# main.net
KiCad netlist of a schematic drawn in Altium Designer
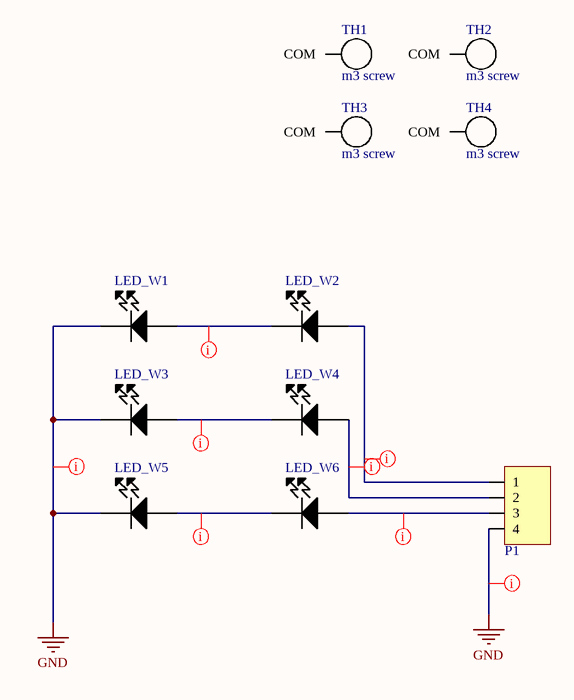
[diagram p0: main.SchDoc]

(export (version "E")
  (design (tool "Eeschema 10.0.6"))
  (components
    (comp (ref "LED_W1")
      (value "MP-3030-210H-40-95")
      (footprint "MP-3030-210H-40-95")
      (description "White 4000K neutral 1.5W 95CRI SMT3030 LED 6V 150mA")
      (libsource (lib "ScienceComponents") (part "MP-3030-210H-40-95"))
    )
    (comp (ref "LED_W2")
      (value "MP-3030-210H-40-95")
      (footprint "MP-3030-210H-40-95")
      (description "White 4000K neutral 1.5W 95CRI SMT3030 LED 6V 150mA")
      (libsource (lib "ScienceComponents") (part "MP-3030-210H-40-95"))
    )
    (comp (ref "LED_W3")
      (value "MP-3030-210H-40-95")
      (footprint "MP-3030-210H-40-95")
      (description "White 4000K neutral 1.5W 95CRI SMT3030 LED 6V 150mA")
      (libsource (lib "ScienceComponents") (part "MP-3030-210H-40-95"))
    )
    (comp (ref "LED_W4")
      (value "MP-3030-210H-40-95")
      (footprint "MP-3030-210H-40-95")
      (description "White 4000K neutral 1.5W 95CRI SMT3030 LED 6V 150mA")
      (libsource (lib "ScienceComponents") (part "MP-3030-210H-40-95"))
    )
    (comp (ref "LED_W5")
      (value "MP-3030-210H-40-95")
      (footprint "MP-3030-210H-40-95")
      (description "White 4000K neutral 1.5W 95CRI SMT3030 LED 6V 150mA")
      (libsource (lib "ScienceComponents") (part "MP-3030-210H-40-95"))
    )
    (comp (ref "LED_W6")
      (value "MP-3030-210H-40-95")
      (footprint "MP-3030-210H-40-95")
      (description "White 4000K neutral 1.5W 95CRI SMT3030 LED 6V 150mA")
      (libsource (lib "ScienceComponents") (part "MP-3030-210H-40-95"))
    )
    (comp (ref "P1")
      (value "Mini-Fit Jr 4 Pos")
      (footprint "MOLEX 0039281043")
      (libsource (lib "RSX_Connectors") (part "Molex 0039281043"))
    )
    (comp (ref "TH1")
      (value "m3 screw")
      (footprint "m3screw")
      (libsource (lib "ScienceComponents") (part "m3 screw"))
    )
    (comp (ref "TH2")
      (value "m3 screw")
      (footprint "m3screw")
      (libsource (lib "ScienceComponents") (part "m3 screw"))
    )
    (comp (ref "TH3")
      (value "m3 screw")
      (footprint "m3screw")
      (libsource (lib "ScienceComponents") (part "m3 screw"))
    )
    (comp (ref "TH4")
      (value "m3 screw")
      (footprint "m3screw")
      (libsource (lib "ScienceComponents") (part "m3 screw"))
    )
  )
  (nets
    (net (code "1") (name "GND") (class "Default")
      (node (ref "LED_W1") (pin "1") (pinfunction "-_1") (pintype "passive"))
      (node (ref "LED_W3") (pin "1") (pinfunction "-_1") (pintype "passive"))
      (node (ref "LED_W5") (pin "1") (pinfunction "-_1") (pintype "passive"))
      (node (ref "P1") (pin "4") (pinfunction "4_4") (pintype "passive"))
    )
    (net (code "2") (name "Net-(LED_W1-+)") (class "Default")
      (node (ref "LED_W1") (pin "2") (pinfunction "+_2") (pintype "passive"))
      (node (ref "LED_W2") (pin "1") (pinfunction "-_1") (pintype "passive"))
    )
    (net (code "3") (name "Net-(LED_W2-+)") (class "Default")
      (node (ref "LED_W2") (pin "2") (pinfunction "+_2") (pintype "passive"))
      (node (ref "P1") (pin "1") (pinfunction "1_1") (pintype "passive"))
    )
    (net (code "4") (name "Net-(LED_W3-+)") (class "Default")
      (node (ref "LED_W3") (pin "2") (pinfunction "+_2") (pintype "passive"))
      (node (ref "LED_W4") (pin "1") (pinfunction "-_1") (pintype "passive"))
    )
    (net (code "5") (name "Net-(LED_W4-+)") (class "Default")
      (node (ref "LED_W4") (pin "2") (pinfunction "+_2") (pintype "passive"))
      (node (ref "P1") (pin "2") (pinfunction "2_2") (pintype "passive"))
    )
    (net (code "6") (name "Net-(LED_W5-+)") (class "Default")
      (node (ref "LED_W5") (pin "2") (pinfunction "+_2") (pintype "passive"))
      (node (ref "LED_W6") (pin "1") (pinfunction "-_1") (pintype "passive"))
    )
    (net (code "7") (name "Net-(LED_W6-+)") (class "Default")
      (node (ref "LED_W6") (pin "2") (pinfunction "+_2") (pintype "passive"))
      (node (ref "P1") (pin "3") (pinfunction "3_3") (pintype "passive"))
    )
    (net (code "8") (name "unconnected-(TH1-COM-Pad0)") (class "Default")
      (node (ref "TH1") (pin "0") (pinfunction "COM_0") (pintype "passive"))
    )
    (net (code "9") (name "unconnected-(TH2-COM-Pad0)") (class "Default")
      (node (ref "TH2") (pin "0") (pinfunction "COM_0") (pintype "passive"))
    )
    (net (code "10") (name "unconnected-(TH3-COM-Pad0)") (class "Default")
      (node (ref "TH3") (pin "0") (pinfunction "COM_0") (pintype "passive"))
    )
    (net (code "11") (name "unconnected-(TH4-COM-Pad0)") (class "Default")
      (node (ref "TH4") (pin "0") (pinfunction "COM_0") (pintype "passive"))
    )
  )
)
